# motordriver-v3_1_config_IO.net
KiCad netlist of a schematic drawn in Altium Designer
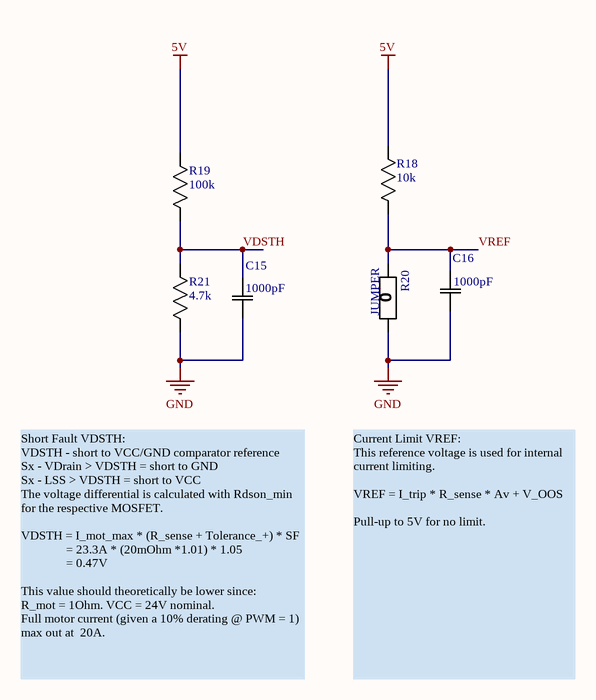
[diagram p0: motordriver-v3.1_config_IO.SchDoc]

(export (version "E")
  (design (tool "Eeschema 10.0.6"))
  (components
    (comp (ref "C15")
      (value "1000pF")
      (footprint "0805")
      (description "CAP CER 1000PF 50V X7R 0603/0805")
      (fields (field (name "TOLERANCE") "10%"))
      (libsource (lib "AltiumLibraries") (part "CAP 1000pF 50V"))
    )
    (comp (ref "C16")
      (value "1000pF")
      (footprint "0805")
      (description "CAP CER 1000PF 50V X7R 0603/0805")
      (fields (field (name "TOLERANCE") "10%"))
      (libsource (lib "AltiumLibraries") (part "CAP 1000pF 50V"))
    )
    (comp (ref "R18")
      (value "10k")
      (footprint "0805")
      (description "RES SMD 10K OHM 1% 1/8W 0805")
      (fields (field (name "TOLERANCE") "1%"))
      (libsource (lib "AltiumLibraries") (part "RES 10k 1/8W - 1%"))
    )
    (comp (ref "R19")
      (value "100k")
      (footprint "0805")
      (description "RES SMD 100K OHM 1% 1/8W 0805")
      (fields (field (name "TOLERANCE") "1%"))
      (libsource (lib "AltiumLibraries") (part "RES 100k 1/8W - 1%"))
    )
    (comp (ref "R20")
      (value "JUMPER")
      (footprint "0805")
      (description "RES SMD 0 OHM JUMPER GENERIC 0805")
      (libsource (lib "AltiumLibraries") (part "RES 0 JUMPER"))
    )
    (comp (ref "R21")
      (value "4.7k")
      (footprint "0805")
      (description "RES SMD 4.7k OHM 1% 1/8W 0805")
      (fields (field (name "TOLERANCE") "1%"))
      (libsource (lib "AltiumLibraries") (part "RES 4.7k 1/8W - 1%"))
    )
  )
  (nets
    (net (code "1") (name "/VDSTH") (class "Default")
      (node (ref "C15") (pin "2") (pinfunction "C2_2") (pintype "passive"))
      (node (ref "R19") (pin "2") (pinfunction "R2_2") (pintype "passive"))
      (node (ref "R21") (pin "1") (pinfunction "R1_1") (pintype "passive"))
    )
    (net (code "2") (name "/VREF") (class "Default")
      (node (ref "C16") (pin "2") (pinfunction "C2_2") (pintype "passive"))
      (node (ref "R18") (pin "2") (pinfunction "R2_2") (pintype "passive"))
      (node (ref "R20") (pin "2") (pinfunction "R2_2") (pintype "passive"))
    )
    (net (code "3") (name "5V") (class "Default")
      (node (ref "R18") (pin "1") (pinfunction "R1_1") (pintype "passive"))
      (node (ref "R19") (pin "1") (pinfunction "R1_1") (pintype "passive"))
    )
    (net (code "4") (name "GND") (class "Default")
      (node (ref "C15") (pin "1") (pinfunction "C1_1") (pintype "passive"))
      (node (ref "C16") (pin "1") (pinfunction "C1_1") (pintype "passive"))
      (node (ref "R20") (pin "1") (pinfunction "R1_1") (pintype "passive"))
      (node (ref "R21") (pin "2") (pinfunction "R2_2") (pintype "passive"))
    )
  )
)
